# OLED.net
KiCad netlist of a schematic drawn in Altium Designer
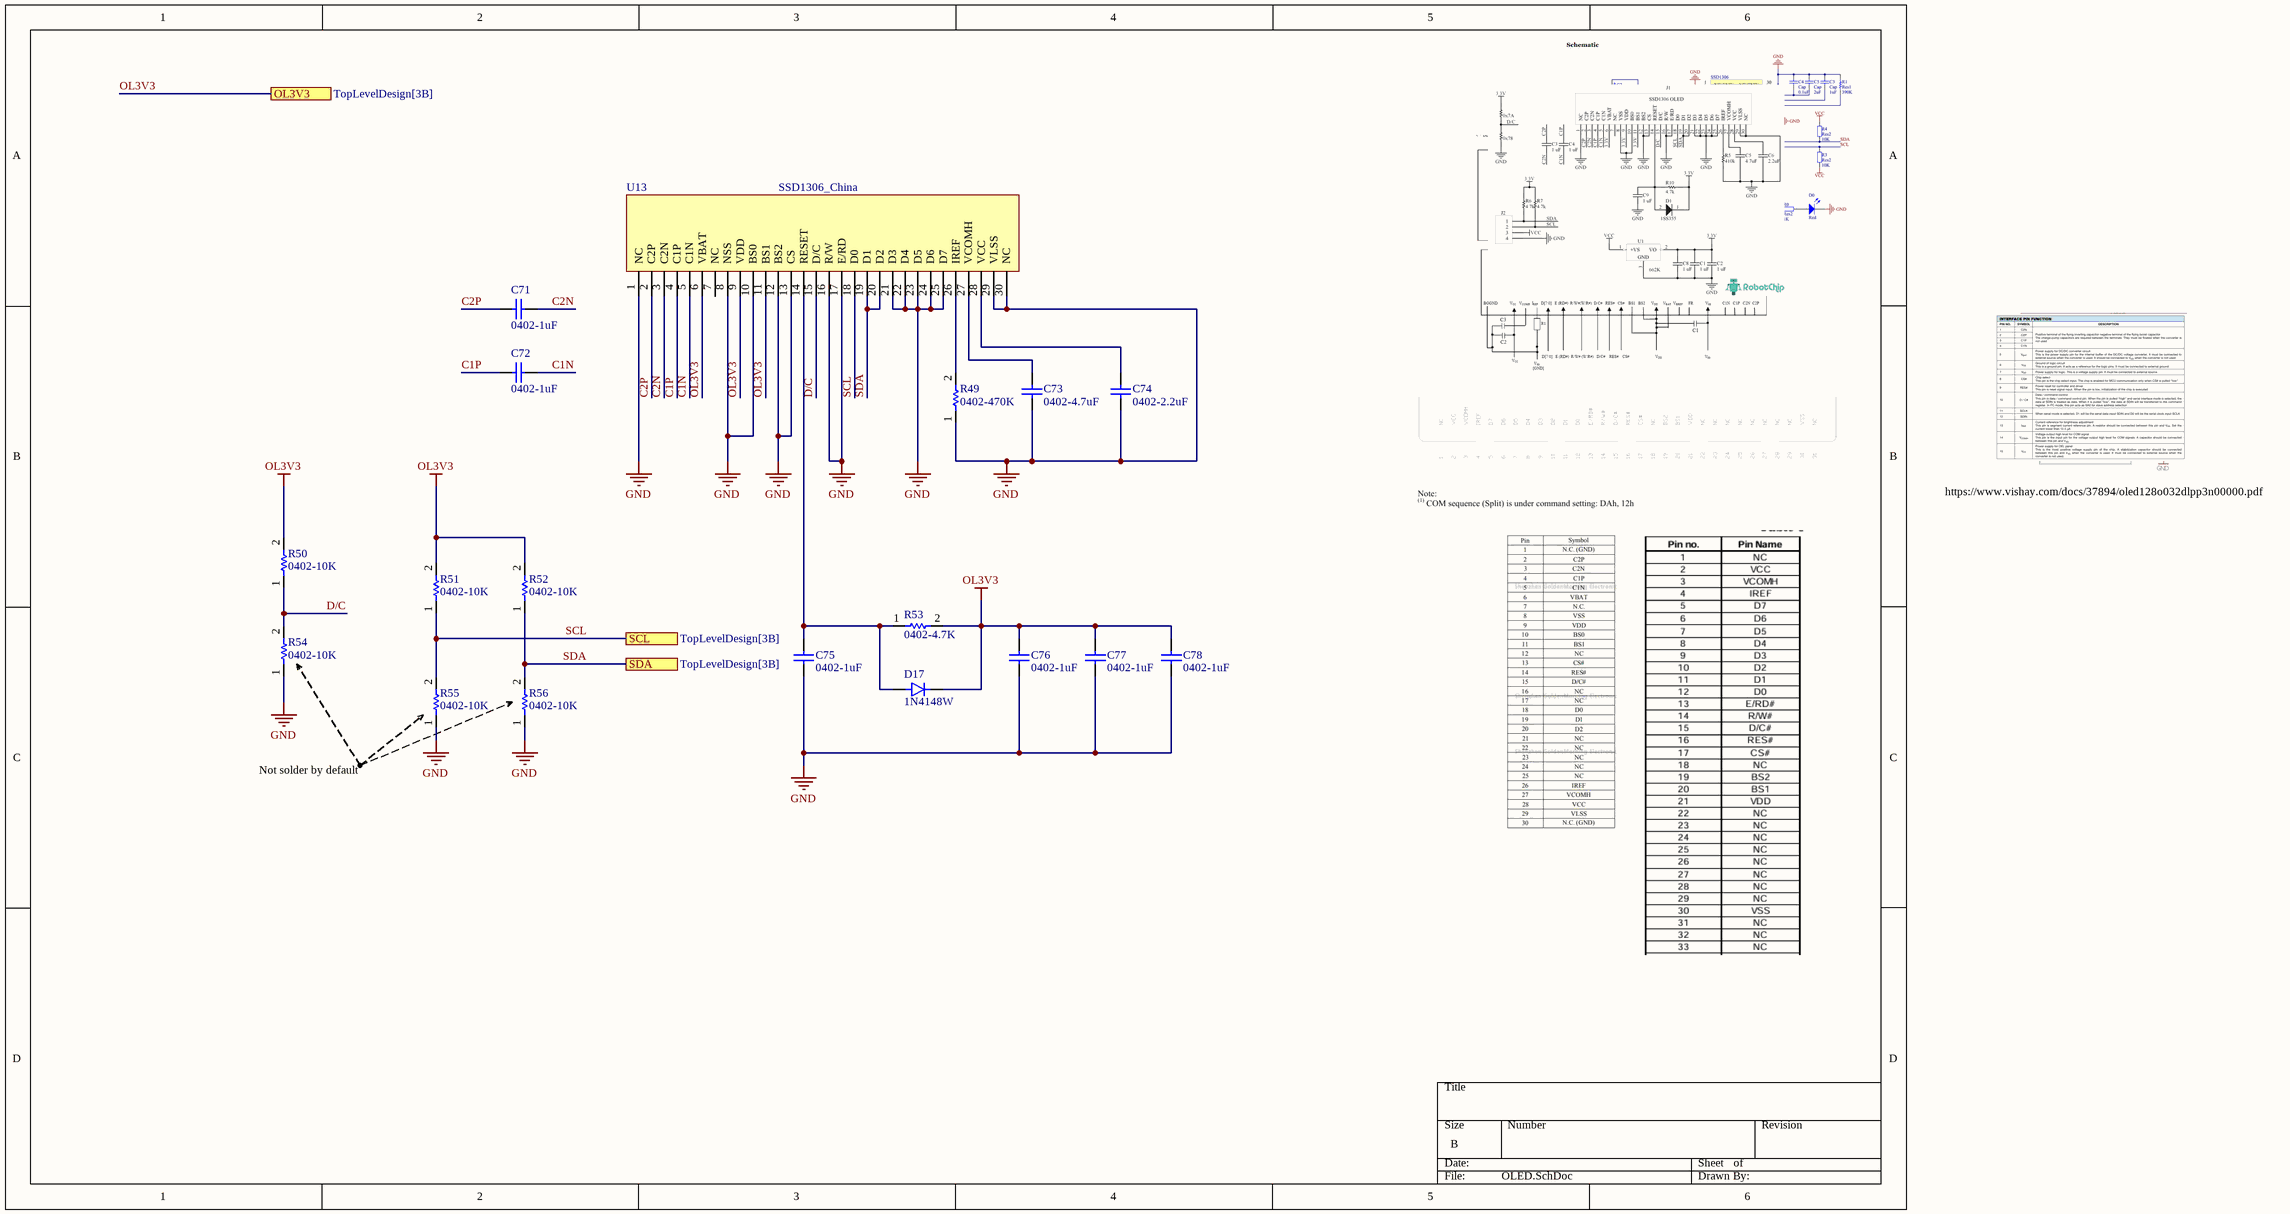
[diagram p0: OLED.SchDoc]

(export (version "E")
  (design (tool "Eeschema 10.0.6"))
  (components
    (comp (ref "C71")
      (value "0402-1uF")
      (footprint "CAPC0402(1005)60_N")
      (description "Capacitor 1uF 0402s")
      (fields (field (name "TOLERANCE") "20%"))
      (libsource (lib "") (part "0402_1"))
    )
    (comp (ref "C72")
      (value "0402-1uF")
      (footprint "CAPC0402(1005)60_N")
      (description "Capacitor 1uF 0402s")
      (fields (field (name "TOLERANCE") "20%"))
      (libsource (lib "") (part "0402_1"))
    )
    (comp (ref "C73")
      (value "0402-4.7uF")
      (footprint "CAPC0402(1005)60_N")
      (description "Capacitor 4.7uF 0402")
      (fields (field (name "TOLERANCE") "20%"))
      (libsource (lib "") (part "0402_1"))
    )
    (comp (ref "C74")
      (value "0402-2.2uF")
      (footprint "CAPC0402(1005)60_N")
      (description "Capacitor 2.2uF 0402")
      (fields (field (name "TOLERANCE") "20%"))
      (libsource (lib "") (part "0402_1"))
    )
    (comp (ref "C75")
      (value "0402-1uF")
      (footprint "CAPC0402(1005)60_N")
      (description "Capacitor 1uF 0402s")
      (fields (field (name "TOLERANCE") "20%"))
      (libsource (lib "") (part "0402_1"))
    )
    (comp (ref "C76")
      (value "0402-1uF")
      (footprint "CAPC0402(1005)60_N")
      (description "Capacitor 1uF 0402s")
      (fields (field (name "TOLERANCE") "20%"))
      (libsource (lib "") (part "0402_1"))
    )
    (comp (ref "C77")
      (value "0402-1uF")
      (footprint "CAPC0402(1005)60_N")
      (description "Capacitor 1uF 0402s")
      (fields (field (name "TOLERANCE") "20%"))
      (libsource (lib "") (part "0402_1"))
    )
    (comp (ref "C78")
      (value "0402-1uF")
      (footprint "CAPC0402(1005)60_N")
      (description "Capacitor 1uF 0402s")
      (fields (field (name "TOLERANCE") "20%"))
      (libsource (lib "") (part "0402_1"))
    )
    (comp (ref "D17")
      (value "1N4148W")
      (footprint "SODFL3816X120N")
      (libsource (lib "Tin Tran") (part "1N4148W"))
    )
    (comp (ref "R49")
      (value "0402-470K")
      (footprint "R-0402-10K")
      (description "RES 0402 470K")
      (libsource (lib "Tin Tran") (part "0402"))
    )
    (comp (ref "R50")
      (value "0402-10K")
      (footprint "R-0402-10K")
      (description "RES 0402 10K")
      (libsource (lib "Tin Tran") (part "0402"))
    )
    (comp (ref "R51")
      (value "0402-10K")
      (footprint "R-0402-10K")
      (description "RES 0402 10K")
      (libsource (lib "Tin Tran") (part "0402"))
    )
    (comp (ref "R52")
      (value "0402-10K")
      (footprint "R-0402-10K")
      (description "RES 0402 10K")
      (libsource (lib "Tin Tran") (part "0402"))
    )
    (comp (ref "R53")
      (value "0402-4.7K")
      (footprint "R-0402-10K")
      (description "RES 0402 4.7K")
      (libsource (lib "Tin Tran") (part "0402"))
    )
    (comp (ref "R54")
      (value "0402-10K")
      (footprint "R-0402-10K")
      (description "RES 0402 10K")
      (libsource (lib "Tin Tran") (part "0402"))
    )
    (comp (ref "R55")
      (value "0402-10K")
      (footprint "R-0402-10K")
      (description "RES 0402 10K")
      (libsource (lib "Tin Tran") (part "0402"))
    )
    (comp (ref "R56")
      (value "0402-10K")
      (footprint "R-0402-10K")
      (description "RES 0402 10K")
      (libsource (lib "Tin Tran") (part "0402"))
    )
    (comp (ref "U13")
      (value "SSD1306_China")
      (footprint "SSD1306_China-Footprint-1")
      (description "SSD1306_China , 0.96 inch display")
      (libsource (lib "Tin Tran") (part "SSD1306_China"))
    )
  )
  (nets
    (net (code "1") (name "/C1N") (class "Default")
      (node (ref "C72") (pin "1") (pinfunction "1_1") (pintype "passive"))
      (node (ref "U13") (pin "5") (pinfunction "C1N_5") (pintype "passive"))
    )
    (net (code "2") (name "/C1P") (class "Default")
      (node (ref "C72") (pin "2") (pinfunction "2_2") (pintype "passive"))
      (node (ref "U13") (pin "4") (pinfunction "C1P_4") (pintype "passive"))
    )
    (net (code "3") (name "/C2N") (class "Default")
      (node (ref "C71") (pin "1") (pinfunction "1_1") (pintype "passive"))
      (node (ref "U13") (pin "3") (pinfunction "C2N_3") (pintype "passive"))
    )
    (net (code "4") (name "/C2P") (class "Default")
      (node (ref "C71") (pin "2") (pinfunction "2_2") (pintype "passive"))
      (node (ref "U13") (pin "2") (pinfunction "C2P_2") (pintype "passive"))
    )
    (net (code "5") (name "/D{slash}C") (class "Default")
      (node (ref "R50") (pin "1") (pinfunction "1_1") (pintype "passive"))
      (node (ref "R54") (pin "2") (pinfunction "2_2") (pintype "passive"))
      (node (ref "U13") (pin "15") (pinfunction "D/C_15") (pintype "passive"))
    )
    (net (code "6") (name "/SCL") (class "Default")
      (node (ref "R51") (pin "1") (pinfunction "1_1") (pintype "passive"))
      (node (ref "R55") (pin "2") (pinfunction "2_2") (pintype "passive"))
      (node (ref "U13") (pin "18") (pinfunction "D0_18") (pintype "passive"))
    )
    (net (code "7") (name "/SDA") (class "Default")
      (node (ref "R52") (pin "1") (pinfunction "1_1") (pintype "passive"))
      (node (ref "R56") (pin "2") (pinfunction "2_2") (pintype "passive"))
      (node (ref "U13") (pin "19") (pinfunction "D1_19") (pintype "passive"))
      (node (ref "U13") (pin "20") (pinfunction "D2_20") (pintype "passive"))
    )
    (net (code "8") (name "GND") (class "Default")
      (node (ref "C73") (pin "1") (pinfunction "1_1") (pintype "passive"))
      (node (ref "C74") (pin "1") (pinfunction "1_1") (pintype "passive"))
      (node (ref "C75") (pin "1") (pinfunction "1_1") (pintype "passive"))
      (node (ref "C76") (pin "1") (pinfunction "1_1") (pintype "passive"))
      (node (ref "C77") (pin "1") (pinfunction "1_1") (pintype "passive"))
      (node (ref "C78") (pin "1") (pinfunction "1_1") (pintype "passive"))
      (node (ref "R49") (pin "1") (pinfunction "1_1") (pintype "passive"))
      (node (ref "R54") (pin "1") (pinfunction "1_1") (pintype "passive"))
      (node (ref "R55") (pin "1") (pinfunction "1_1") (pintype "passive"))
      (node (ref "R56") (pin "1") (pinfunction "1_1") (pintype "passive"))
      (node (ref "U13") (pin "1") (pinfunction "NC_1") (pintype "passive"))
      (node (ref "U13") (pin "10") (pinfunction "BS0_10") (pintype "passive"))
      (node (ref "U13") (pin "12") (pinfunction "BS2_12") (pintype "passive"))
      (node (ref "U13") (pin "13") (pinfunction "CS_13") (pintype "passive"))
      (node (ref "U13") (pin "16") (pinfunction "R/W_16") (pintype "passive"))
      (node (ref "U13") (pin "17") (pinfunction "E/RD_17") (pintype "passive"))
      (node (ref "U13") (pin "21") (pinfunction "D3_21") (pintype "passive"))
      (node (ref "U13") (pin "22") (pinfunction "D4_22") (pintype "passive"))
      (node (ref "U13") (pin "23") (pinfunction "D5_23") (pintype "passive"))
      (node (ref "U13") (pin "24") (pinfunction "D6_24") (pintype "passive"))
      (node (ref "U13") (pin "25") (pinfunction "D7_25") (pintype "passive"))
      (node (ref "U13") (pin "29") (pinfunction "VLSS_29") (pintype "passive"))
      (node (ref "U13") (pin "30") (pinfunction "NC_30") (pintype "passive"))
      (node (ref "U13") (pin "8") (pinfunction "NSS_8") (pintype "passive"))
    )
    (net (code "9") (name "Net-(U13-IREF)") (class "Default")
      (node (ref "R49") (pin "2") (pinfunction "2_2") (pintype "passive"))
      (node (ref "U13") (pin "26") (pinfunction "IREF_26") (pintype "passive"))
    )
    (net (code "10") (name "Net-(U13-RESET)") (class "Default")
      (node (ref "C75") (pin "2") (pinfunction "2_2") (pintype "passive"))
      (node (ref "D17") (pin "A") (pinfunction "A_A") (pintype "passive"))
      (node (ref "R53") (pin "1") (pinfunction "1_1") (pintype "passive"))
      (node (ref "U13") (pin "14") (pinfunction "RESET_14") (pintype "passive"))
    )
    (net (code "11") (name "Net-(U13-VCC)") (class "Default")
      (node (ref "C74") (pin "2") (pinfunction "2_2") (pintype "passive"))
      (node (ref "U13") (pin "28") (pinfunction "VCC_28") (pintype "passive"))
    )
    (net (code "12") (name "Net-(U13-VCOMH)") (class "Default")
      (node (ref "C73") (pin "2") (pinfunction "2_2") (pintype "passive"))
      (node (ref "U13") (pin "27") (pinfunction "VCOMH_27") (pintype "passive"))
    )
    (net (code "13") (name "OL3V3") (class "Default")
      (node (ref "C76") (pin "2") (pinfunction "2_2") (pintype "passive"))
      (node (ref "C77") (pin "2") (pinfunction "2_2") (pintype "passive"))
      (node (ref "C78") (pin "2") (pinfunction "2_2") (pintype "passive"))
      (node (ref "D17") (pin "C") (pinfunction "K_C") (pintype "passive"))
      (node (ref "R50") (pin "2") (pinfunction "2_2") (pintype "passive"))
      (node (ref "R51") (pin "2") (pinfunction "2_2") (pintype "passive"))
      (node (ref "R52") (pin "2") (pinfunction "2_2") (pintype "passive"))
      (node (ref "R53") (pin "2") (pinfunction "2_2") (pintype "passive"))
      (node (ref "U13") (pin "11") (pinfunction "BS1_11") (pintype "passive"))
      (node (ref "U13") (pin "6") (pinfunction "VBAT_6") (pintype "passive"))
      (node (ref "U13") (pin "9") (pinfunction "VDD_9") (pintype "passive"))
    )
    (net (code "14") (name "unconnected-(U13-NC-Pad7)") (class "Default")
      (node (ref "U13") (pin "7") (pinfunction "NC_7") (pintype "passive"))
    )
  )
)
